# ParallelVias.net
KiCad netlist of a schematic drawn in Altium Designer
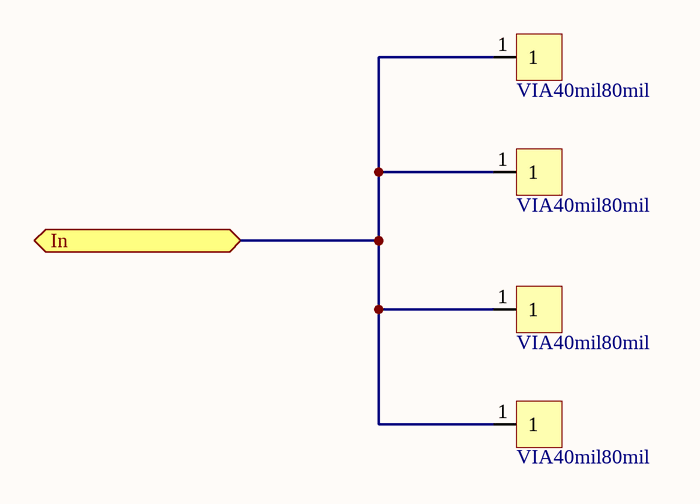
[diagram p0: ParallelVias.SchDoc]

(export (version "E")
  (design (tool "Eeschema 10.0.6"))
  (components
    (comp (ref "V1")
      (value "VIA40mil80mil")
      (footprint "VIA40mil80mil")
      (libsource (lib "AdamsParts") (part "VIA40mil80mil"))
    )
    (comp (ref "V2")
      (value "VIA40mil80mil")
      (footprint "VIA40mil80mil")
      (libsource (lib "AdamsParts") (part "VIA40mil80mil"))
    )
    (comp (ref "V3")
      (value "VIA40mil80mil")
      (footprint "VIA40mil80mil")
      (libsource (lib "AdamsParts") (part "VIA40mil80mil"))
    )
    (comp (ref "V4")
      (value "VIA40mil80mil")
      (footprint "VIA40mil80mil")
      (libsource (lib "AdamsParts") (part "VIA40mil80mil"))
    )
  )
  (nets
    (net (code "1") (name "/In") (class "Default")
      (node (ref "V1") (pin "1") (pinfunction "1_1") (pintype "passive"))
      (node (ref "V2") (pin "1") (pinfunction "1_1") (pintype "passive"))
      (node (ref "V3") (pin "1") (pinfunction "1_1") (pintype "passive"))
      (node (ref "V4") (pin "1") (pinfunction "1_1") (pintype "passive"))
    )
  )
)
